# Keg_Cop_-_Devel_TH.net
KiCad netlist of a schematic drawn in EAGLE
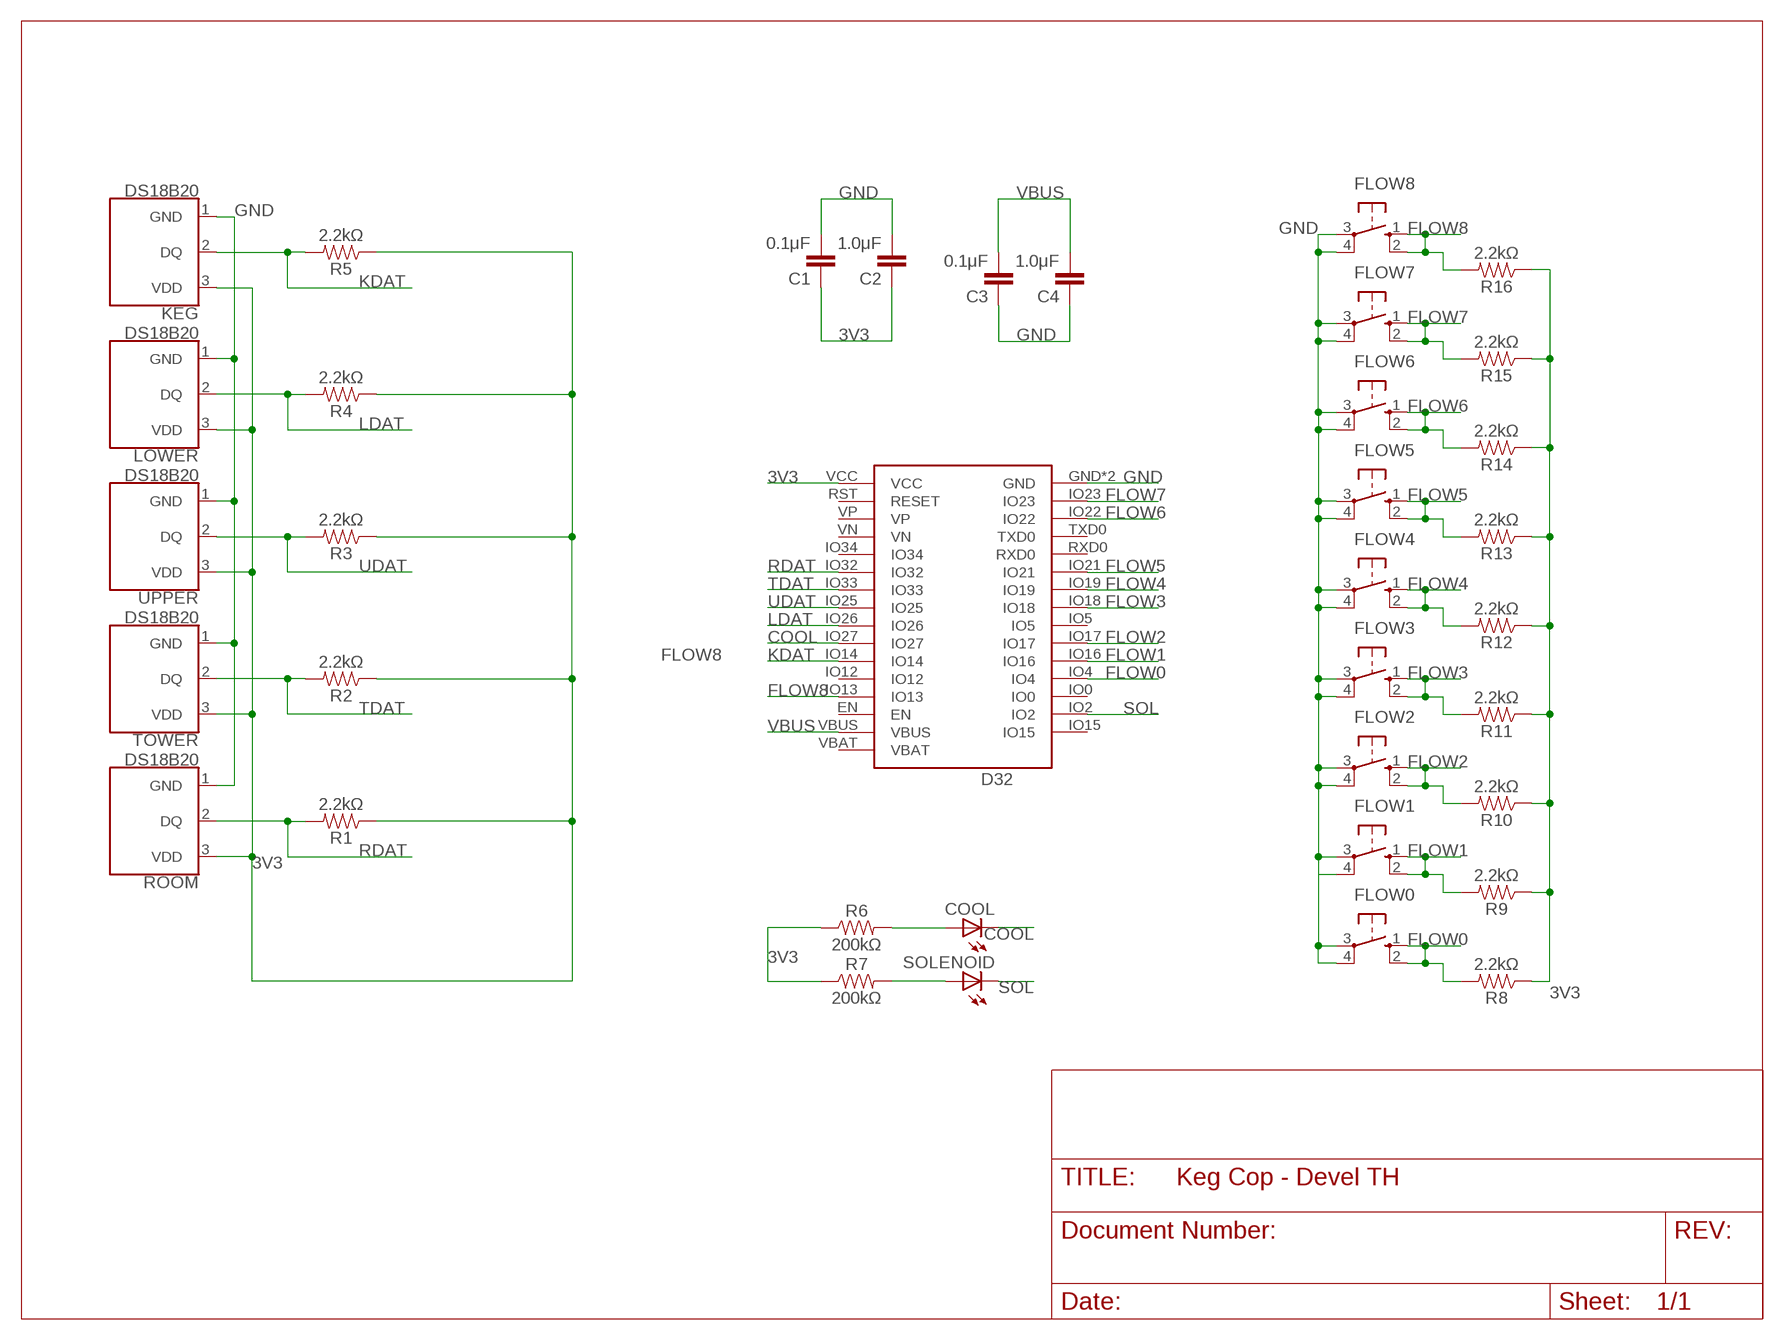
[diagram p0: schematic, sheet 1]

(export (version "E")
  (design (tool "Eeschema 10.0.6"))
  (components
    (comp (ref "C1")
      (value "0.1μF")
      (footprint "eagle-import:CAP_PTH-2.54")
      (libsource (lib "eagle-import") (part "CAP_CERAMIC_2.54"))
    )
    (comp (ref "C2")
      (value "1.0μF")
      (footprint "eagle-import:CAP_PTH-2.54")
      (libsource (lib "eagle-import") (part "CAP_CERAMIC_2.54"))
    )
    (comp (ref "C3")
      (value "0.1μF")
      (footprint "eagle-import:CAP_PTH-2.54")
      (libsource (lib "eagle-import") (part "CAP_CERAMIC_2.54"))
    )
    (comp (ref "C4")
      (value "1.0μF")
      (footprint "eagle-import:CAP_PTH-2.54")
      (libsource (lib "eagle-import") (part "CAP_CERAMIC_2.54"))
    )
    (comp (ref "COOL")
      (value "LED3MM")
      (footprint "eagle-import:LED3MM")
      (libsource (lib "eagle-import") (part "LED3MM"))
    )
    (comp (ref "D32")
      (value "Lolin D32")
      (footprint "eagle-import:D32_NO_BATT")
      (fields (field (name "SPICEPREFIX") "X"))
      (libsource (lib "eagle-import") (part "WEMOS-D32D32_NO_BATT"))
    )
    (comp (ref "FLOW0")
      (value "10-XX")
      (footprint "eagle-import:B3F-10XX")
      (fields (field (name "MPN") "B3F-1000"))
      (libsource (lib "eagle-import") (part "10-XX"))
    )
    (comp (ref "FLOW1")
      (value "10-XX")
      (footprint "eagle-import:B3F-10XX")
      (fields (field (name "MPN") "B3F-1000"))
      (libsource (lib "eagle-import") (part "10-XX"))
    )
    (comp (ref "FLOW2")
      (value "10-XX")
      (footprint "eagle-import:B3F-10XX")
      (fields (field (name "MPN") "B3F-1000"))
      (libsource (lib "eagle-import") (part "10-XX"))
    )
    (comp (ref "FLOW3")
      (value "10-XX")
      (footprint "eagle-import:B3F-10XX")
      (fields (field (name "MPN") "B3F-1000"))
      (libsource (lib "eagle-import") (part "10-XX"))
    )
    (comp (ref "FLOW4")
      (value "10-XX")
      (footprint "eagle-import:B3F-10XX")
      (fields (field (name "MPN") "B3F-1000"))
      (libsource (lib "eagle-import") (part "10-XX"))
    )
    (comp (ref "FLOW5")
      (value "10-XX")
      (footprint "eagle-import:B3F-10XX")
      (fields (field (name "MPN") "B3F-1000"))
      (libsource (lib "eagle-import") (part "10-XX"))
    )
    (comp (ref "FLOW6")
      (value "10-XX")
      (footprint "eagle-import:B3F-10XX")
      (fields (field (name "MPN") "B3F-1000"))
      (libsource (lib "eagle-import") (part "10-XX"))
    )
    (comp (ref "FLOW7")
      (value "10-XX")
      (footprint "eagle-import:B3F-10XX")
      (fields (field (name "MPN") "B3F-1000"))
      (libsource (lib "eagle-import") (part "10-XX"))
    )
    (comp (ref "FLOW8")
      (value "10-XX")
      (footprint "eagle-import:B3F-10XX")
      (fields (field (name "MPN") "B3F-1000"))
      (libsource (lib "eagle-import") (part "10-XX"))
    )
    (comp (ref "KEG")
      (value "DS18B20")
      (footprint "eagle-import:TO-92-AMMO")
      (libsource (lib "eagle-import") (part "DS18B20"))
    )
    (comp (ref "LOWER")
      (value "DS18B20")
      (footprint "eagle-import:TO-92-AMMO")
      (libsource (lib "eagle-import") (part "DS18B20"))
    )
    (comp (ref "R1")
      (value "2.2kΩ")
      (footprint "eagle-import:AXIAL-0.3")
      (libsource (lib "eagle-import") (part "RESISTORAXIAL-0.3"))
    )
    (comp (ref "R2")
      (value "2.2kΩ")
      (footprint "eagle-import:AXIAL-0.3")
      (libsource (lib "eagle-import") (part "RESISTORAXIAL-0.3"))
    )
    (comp (ref "R3")
      (value "2.2kΩ")
      (footprint "eagle-import:AXIAL-0.3")
      (libsource (lib "eagle-import") (part "RESISTORAXIAL-0.3"))
    )
    (comp (ref "R4")
      (value "2.2kΩ")
      (footprint "eagle-import:AXIAL-0.3")
      (libsource (lib "eagle-import") (part "RESISTORAXIAL-0.3"))
    )
    (comp (ref "R5")
      (value "2.2kΩ")
      (footprint "eagle-import:AXIAL-0.3")
      (libsource (lib "eagle-import") (part "RESISTORAXIAL-0.3"))
    )
    (comp (ref "R6")
      (value "200kΩ")
      (footprint "eagle-import:AXIAL-0.3")
      (libsource (lib "eagle-import") (part "RESISTORAXIAL-0.3"))
    )
    (comp (ref "R7")
      (value "200kΩ")
      (footprint "eagle-import:AXIAL-0.3")
      (libsource (lib "eagle-import") (part "RESISTORAXIAL-0.3"))
    )
    (comp (ref "R8")
      (value "2.2kΩ")
      (footprint "eagle-import:AXIAL-0.3")
      (libsource (lib "eagle-import") (part "RESISTORAXIAL-0.3"))
    )
    (comp (ref "R9")
      (value "2.2kΩ")
      (footprint "eagle-import:AXIAL-0.3")
      (libsource (lib "eagle-import") (part "RESISTORAXIAL-0.3"))
    )
    (comp (ref "R10")
      (value "2.2kΩ")
      (footprint "eagle-import:AXIAL-0.3")
      (libsource (lib "eagle-import") (part "RESISTORAXIAL-0.3"))
    )
    (comp (ref "R11")
      (value "2.2kΩ")
      (footprint "eagle-import:AXIAL-0.3")
      (libsource (lib "eagle-import") (part "RESISTORAXIAL-0.3"))
    )
    (comp (ref "R12")
      (value "2.2kΩ")
      (footprint "eagle-import:AXIAL-0.3")
      (libsource (lib "eagle-import") (part "RESISTORAXIAL-0.3"))
    )
    (comp (ref "R13")
      (value "2.2kΩ")
      (footprint "eagle-import:AXIAL-0.3")
      (libsource (lib "eagle-import") (part "RESISTORAXIAL-0.3"))
    )
    (comp (ref "R14")
      (value "2.2kΩ")
      (footprint "eagle-import:AXIAL-0.3")
      (libsource (lib "eagle-import") (part "RESISTORAXIAL-0.3"))
    )
    (comp (ref "R15")
      (value "2.2kΩ")
      (footprint "eagle-import:AXIAL-0.3")
      (libsource (lib "eagle-import") (part "RESISTORAXIAL-0.3"))
    )
    (comp (ref "R16")
      (value "2.2kΩ")
      (footprint "eagle-import:AXIAL-0.3")
      (libsource (lib "eagle-import") (part "RESISTORAXIAL-0.3"))
    )
    (comp (ref "ROOM")
      (value "DS18B20")
      (footprint "eagle-import:TO-92-AMMO")
      (libsource (lib "eagle-import") (part "DS18B20"))
    )
    (comp (ref "SOLENOID")
      (value "LED3MM")
      (footprint "eagle-import:LED3MM")
      (libsource (lib "eagle-import") (part "LED3MM"))
    )
    (comp (ref "TOWER")
      (value "DS18B20")
      (footprint "eagle-import:TO-92-AMMO")
      (libsource (lib "eagle-import") (part "DS18B20"))
    )
    (comp (ref "UPPER")
      (value "DS18B20")
      (footprint "eagle-import:TO-92-AMMO")
      (libsource (lib "eagle-import") (part "DS18B20"))
    )
  )
  (nets
    (net (code "1") (name "/3V3") (class "Default")
      (node (ref "C1") (pin "1") (pinfunction "1_1") (pintype "passive"))
      (node (ref "C2") (pin "1") (pinfunction "1_1") (pintype "passive"))
      (node (ref "D32") (pin "VCC") (pinfunction "VCC_VCC") (pintype "power_in"))
      (node (ref "KEG") (pin "3") (pinfunction "VDD_3") (pintype "power_in"))
      (node (ref "LOWER") (pin "3") (pinfunction "VDD_3") (pintype "power_in"))
      (node (ref "R1") (pin "P$1") (pinfunction "1_P$1") (pintype "passive"))
      (node (ref "R10") (pin "P$1") (pinfunction "1_P$1") (pintype "passive"))
      (node (ref "R11") (pin "P$1") (pinfunction "1_P$1") (pintype "passive"))
      (node (ref "R12") (pin "P$1") (pinfunction "1_P$1") (pintype "passive"))
      (node (ref "R13") (pin "P$1") (pinfunction "1_P$1") (pintype "passive"))
      (node (ref "R14") (pin "P$1") (pinfunction "1_P$1") (pintype "passive"))
      (node (ref "R15") (pin "P$1") (pinfunction "1_P$1") (pintype "passive"))
      (node (ref "R16") (pin "P$1") (pinfunction "1_P$1") (pintype "passive"))
      (node (ref "R2") (pin "P$1") (pinfunction "1_P$1") (pintype "passive"))
      (node (ref "R3") (pin "P$1") (pinfunction "1_P$1") (pintype "passive"))
      (node (ref "R4") (pin "P$1") (pinfunction "1_P$1") (pintype "passive"))
      (node (ref "R5") (pin "P$1") (pinfunction "1_P$1") (pintype "passive"))
      (node (ref "R6") (pin "P$1") (pinfunction "1_P$1") (pintype "passive"))
      (node (ref "R7") (pin "P$1") (pinfunction "1_P$1") (pintype "passive"))
      (node (ref "R8") (pin "P$1") (pinfunction "1_P$1") (pintype "passive"))
      (node (ref "R9") (pin "P$1") (pinfunction "1_P$1") (pintype "passive"))
      (node (ref "ROOM") (pin "3") (pinfunction "VDD_3") (pintype "power_in"))
      (node (ref "TOWER") (pin "3") (pinfunction "VDD_3") (pintype "power_in"))
      (node (ref "UPPER") (pin "3") (pinfunction "VDD_3") (pintype "power_in"))
    )
    (net (code "2") (name "/COOL") (class "Default")
      (node (ref "COOL") (pin "K") (pinfunction "C_K") (pintype "passive"))
      (node (ref "D32") (pin "IO27") (pinfunction "IO27_IO27") (pintype "bidirectional"))
    )
    (net (code "3") (name "/FLOW0") (class "Default")
      (node (ref "D32") (pin "IO4") (pinfunction "IO4_IO4") (pintype "bidirectional"))
      (node (ref "FLOW0") (pin "1") (pinfunction "S_1") (pintype "passive"))
      (node (ref "FLOW0") (pin "2") (pinfunction "S1_2") (pintype "passive"))
      (node (ref "R8") (pin "P$2") (pinfunction "2_P$2") (pintype "passive"))
    )
    (net (code "4") (name "/FLOW1") (class "Default")
      (node (ref "D32") (pin "IO16") (pinfunction "IO16_IO16") (pintype "bidirectional"))
      (node (ref "FLOW1") (pin "1") (pinfunction "S_1") (pintype "passive"))
      (node (ref "FLOW1") (pin "2") (pinfunction "S1_2") (pintype "passive"))
      (node (ref "R9") (pin "P$2") (pinfunction "2_P$2") (pintype "passive"))
    )
    (net (code "5") (name "/FLOW2") (class "Default")
      (node (ref "D32") (pin "IO17") (pinfunction "IO17_IO17") (pintype "bidirectional"))
      (node (ref "FLOW2") (pin "1") (pinfunction "S_1") (pintype "passive"))
      (node (ref "FLOW2") (pin "2") (pinfunction "S1_2") (pintype "passive"))
      (node (ref "R10") (pin "P$2") (pinfunction "2_P$2") (pintype "passive"))
    )
    (net (code "6") (name "/FLOW3") (class "Default")
      (node (ref "D32") (pin "IO18") (pinfunction "IO18_IO18") (pintype "bidirectional"))
      (node (ref "FLOW3") (pin "1") (pinfunction "S_1") (pintype "passive"))
      (node (ref "FLOW3") (pin "2") (pinfunction "S1_2") (pintype "passive"))
      (node (ref "R11") (pin "P$2") (pinfunction "2_P$2") (pintype "passive"))
    )
    (net (code "7") (name "/FLOW4") (class "Default")
      (node (ref "D32") (pin "IO19") (pinfunction "IO19_IO19") (pintype "bidirectional"))
      (node (ref "FLOW4") (pin "1") (pinfunction "S_1") (pintype "passive"))
      (node (ref "FLOW4") (pin "2") (pinfunction "S1_2") (pintype "passive"))
      (node (ref "R12") (pin "P$2") (pinfunction "2_P$2") (pintype "passive"))
    )
    (net (code "8") (name "/FLOW5") (class "Default")
      (node (ref "D32") (pin "IO21") (pinfunction "IO21_IO21") (pintype "bidirectional"))
      (node (ref "FLOW5") (pin "1") (pinfunction "S_1") (pintype "passive"))
      (node (ref "FLOW5") (pin "2") (pinfunction "S1_2") (pintype "passive"))
      (node (ref "R13") (pin "P$2") (pinfunction "2_P$2") (pintype "passive"))
    )
    (net (code "9") (name "/FLOW6") (class "Default")
      (node (ref "D32") (pin "IO22") (pinfunction "IO22_IO22") (pintype "bidirectional"))
      (node (ref "FLOW6") (pin "1") (pinfunction "S_1") (pintype "passive"))
      (node (ref "FLOW6") (pin "2") (pinfunction "S1_2") (pintype "passive"))
      (node (ref "R14") (pin "P$2") (pinfunction "2_P$2") (pintype "passive"))
    )
    (net (code "10") (name "/FLOW7") (class "Default")
      (node (ref "D32") (pin "IO23") (pinfunction "IO23_IO23") (pintype "bidirectional"))
      (node (ref "FLOW7") (pin "1") (pinfunction "S_1") (pintype "passive"))
      (node (ref "FLOW7") (pin "2") (pinfunction "S1_2") (pintype "passive"))
      (node (ref "R15") (pin "P$2") (pinfunction "2_P$2") (pintype "passive"))
    )
    (net (code "11") (name "/FLOW8") (class "Default")
      (node (ref "D32") (pin "IO13") (pinfunction "IO13_IO13") (pintype "bidirectional"))
      (node (ref "FLOW8") (pin "1") (pinfunction "S_1") (pintype "passive"))
      (node (ref "FLOW8") (pin "2") (pinfunction "S1_2") (pintype "passive"))
      (node (ref "R16") (pin "P$2") (pinfunction "2_P$2") (pintype "passive"))
    )
    (net (code "12") (name "/GND") (class "Default")
      (node (ref "C1") (pin "2") (pinfunction "2_2") (pintype "passive"))
      (node (ref "C2") (pin "2") (pinfunction "2_2") (pintype "passive"))
      (node (ref "C3") (pin "1") (pinfunction "1_1") (pintype "passive"))
      (node (ref "C4") (pin "1") (pinfunction "1_1") (pintype "passive"))
      (node (ref "D32") (pin "GND") (pinfunction "GND_GND") (pintype "power_in"))
      (node (ref "D32") (pin "GND2") (pinfunction "GND_GND2") (pintype "power_in"))
      (node (ref "FLOW0") (pin "3") (pinfunction "P_3") (pintype "passive"))
      (node (ref "FLOW0") (pin "4") (pinfunction "P1_4") (pintype "passive"))
      (node (ref "FLOW1") (pin "3") (pinfunction "P_3") (pintype "passive"))
      (node (ref "FLOW1") (pin "4") (pinfunction "P1_4") (pintype "passive"))
      (node (ref "FLOW2") (pin "3") (pinfunction "P_3") (pintype "passive"))
      (node (ref "FLOW2") (pin "4") (pinfunction "P1_4") (pintype "passive"))
      (node (ref "FLOW3") (pin "3") (pinfunction "P_3") (pintype "passive"))
      (node (ref "FLOW3") (pin "4") (pinfunction "P1_4") (pintype "passive"))
      (node (ref "FLOW4") (pin "3") (pinfunction "P_3") (pintype "passive"))
      (node (ref "FLOW4") (pin "4") (pinfunction "P1_4") (pintype "passive"))
      (node (ref "FLOW5") (pin "3") (pinfunction "P_3") (pintype "passive"))
      (node (ref "FLOW5") (pin "4") (pinfunction "P1_4") (pintype "passive"))
      (node (ref "FLOW6") (pin "3") (pinfunction "P_3") (pintype "passive"))
      (node (ref "FLOW6") (pin "4") (pinfunction "P1_4") (pintype "passive"))
      (node (ref "FLOW7") (pin "3") (pinfunction "P_3") (pintype "passive"))
      (node (ref "FLOW7") (pin "4") (pinfunction "P1_4") (pintype "passive"))
      (node (ref "FLOW8") (pin "3") (pinfunction "P_3") (pintype "passive"))
      (node (ref "FLOW8") (pin "4") (pinfunction "P1_4") (pintype "passive"))
      (node (ref "KEG") (pin "1") (pinfunction "GND_1") (pintype "power_in"))
      (node (ref "LOWER") (pin "1") (pinfunction "GND_1") (pintype "power_in"))
      (node (ref "ROOM") (pin "1") (pinfunction "GND_1") (pintype "power_in"))
      (node (ref "TOWER") (pin "1") (pinfunction "GND_1") (pintype "power_in"))
      (node (ref "UPPER") (pin "1") (pinfunction "GND_1") (pintype "power_in"))
    )
    (net (code "13") (name "/KDAT") (class "Default")
      (node (ref "D32") (pin "IO14") (pinfunction "IO14_IO14") (pintype "bidirectional"))
      (node (ref "KEG") (pin "2") (pinfunction "DQ_2") (pintype "bidirectional"))
      (node (ref "R5") (pin "P$2") (pinfunction "2_P$2") (pintype "passive"))
    )
    (net (code "14") (name "/LDAT") (class "Default")
      (node (ref "D32") (pin "IO26") (pinfunction "IO26_IO26") (pintype "bidirectional"))
      (node (ref "LOWER") (pin "2") (pinfunction "DQ_2") (pintype "bidirectional"))
      (node (ref "R4") (pin "P$2") (pinfunction "2_P$2") (pintype "passive"))
    )
    (net (code "15") (name "/RDAT") (class "Default")
      (node (ref "D32") (pin "IO32") (pinfunction "IO32_IO32") (pintype "bidirectional"))
      (node (ref "R1") (pin "P$2") (pinfunction "2_P$2") (pintype "passive"))
      (node (ref "ROOM") (pin "2") (pinfunction "DQ_2") (pintype "bidirectional"))
    )
    (net (code "16") (name "/SOL") (class "Default")
      (node (ref "D32") (pin "IO2") (pinfunction "IO2_IO2") (pintype "bidirectional"))
      (node (ref "SOLENOID") (pin "K") (pinfunction "C_K") (pintype "passive"))
    )
    (net (code "17") (name "/TDAT") (class "Default")
      (node (ref "D32") (pin "IO33") (pinfunction "IO33_IO33") (pintype "bidirectional"))
      (node (ref "R2") (pin "P$2") (pinfunction "2_P$2") (pintype "passive"))
      (node (ref "TOWER") (pin "2") (pinfunction "DQ_2") (pintype "bidirectional"))
    )
    (net (code "18") (name "/UDAT") (class "Default")
      (node (ref "D32") (pin "IO25") (pinfunction "IO25_IO25") (pintype "bidirectional"))
      (node (ref "R3") (pin "P$2") (pinfunction "2_P$2") (pintype "passive"))
      (node (ref "UPPER") (pin "2") (pinfunction "DQ_2") (pintype "bidirectional"))
    )
    (net (code "19") (name "/VBUS") (class "Default")
      (node (ref "C3") (pin "2") (pinfunction "2_2") (pintype "passive"))
      (node (ref "C4") (pin "2") (pinfunction "2_2") (pintype "passive"))
      (node (ref "D32") (pin "VBUS") (pinfunction "VBUS_VBUS") (pintype "bidirectional"))
    )
    (net (code "20") (name "Net-(R6-2)") (class "Default")
      (node (ref "COOL") (pin "A") (pinfunction "A_A") (pintype "passive"))
      (node (ref "R6") (pin "P$2") (pinfunction "2_P$2") (pintype "passive"))
    )
    (net (code "21") (name "Net-(R7-2)") (class "Default")
      (node (ref "R7") (pin "P$2") (pinfunction "2_P$2") (pintype "passive"))
      (node (ref "SOLENOID") (pin "A") (pinfunction "A_A") (pintype "passive"))
    )
    (net (code "22") (name "unconnected-(D32-PadEN)") (class "Default")
      (node (ref "D32") (pin "EN") (pinfunction "EN_EN") (pintype "bidirectional"))
    )
    (net (code "23") (name "unconnected-(D32-PadIO0)") (class "Default")
      (node (ref "D32") (pin "IO0") (pinfunction "IO0_IO0") (pintype "bidirectional"))
    )
    (net (code "24") (name "unconnected-(D32-PadIO5)") (class "Default")
      (node (ref "D32") (pin "IO5") (pinfunction "IO5_IO5") (pintype "bidirectional"))
    )
    (net (code "25") (name "unconnected-(D32-PadIO12)") (class "Default")
      (node (ref "D32") (pin "IO12") (pinfunction "IO12_IO12") (pintype "bidirectional"))
    )
    (net (code "26") (name "unconnected-(D32-PadIO15)") (class "Default")
      (node (ref "D32") (pin "IO15") (pinfunction "IO15_IO15") (pintype "bidirectional"))
    )
    (net (code "27") (name "unconnected-(D32-PadIO34)") (class "Default")
      (node (ref "D32") (pin "IO34") (pinfunction "IO34_IO34") (pintype "bidirectional"))
    )
    (net (code "28") (name "unconnected-(D32-PadRXD0)") (class "Default")
      (node (ref "D32") (pin "RXD0") (pinfunction "RXD0_RXD0") (pintype "input"))
    )
    (net (code "29") (name "unconnected-(D32-PadTXD0)") (class "Default")
      (node (ref "D32") (pin "TXD0") (pinfunction "TXD0_TXD0") (pintype "output"))
    )
    (net (code "30") (name "unconnected-(D32-PadVBAT)") (class "Default")
      (node (ref "D32") (pin "VBAT") (pinfunction "VBAT_VBAT") (pintype "bidirectional"))
    )
    (net (code "31") (name "unconnected-(D32-PadVN)") (class "Default")
      (node (ref "D32") (pin "VN") (pinfunction "VN_VN") (pintype "bidirectional"))
    )
    (net (code "32") (name "unconnected-(D32-PadVP)") (class "Default")
      (node (ref "D32") (pin "VP") (pinfunction "VP_VP") (pintype "bidirectional"))
    )
    (net (code "33") (name "unconnected-(D32-RESET-PadRST)") (class "Default")
      (node (ref "D32") (pin "RST") (pinfunction "RESET_RST") (pintype "bidirectional"))
    )
  )
)
